# Schematic.net
KiCad netlist of a schematic drawn in EAGLE
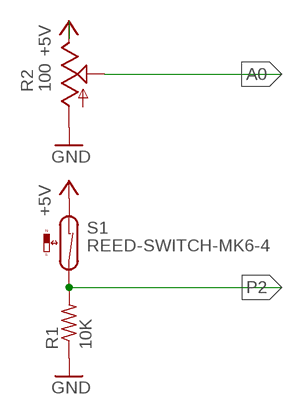
[diagram p0: schematic, sheet 1]

(export (version "E")
  (design (tool "Eeschema 10.0.6"))
  (components
    (comp (ref "R1")
      (value "10K")
      (footprint "eagle-import:0204_5")
      (libsource (lib "eagle-import") (part "R-US_0204/5"))
    )
    (comp (ref "R2")
      (value "100")
      (footprint "eagle-import:CIP20C-4MM")
      (libsource (lib "eagle-import") (part "TRIM_US-CIP20C-4MM"))
    )
    (comp (ref "S1")
      (value "REED-SWITCH-MK6-4")
      (footprint "eagle-import:MK6-4")
      (libsource (lib "eagle-import") (part "REED-SWITCH-MK6-4"))
    )
  )
  (nets
    (net (code "1") (name "+5V") (class "Default")
      (node (ref "R2") (pin "E") (pinfunction "E_E") (pintype "passive"))
      (node (ref "S1") (pin "1") (pinfunction "1_1") (pintype "passive"))
    )
    (net (code "2") (name "A0") (class "Default")
      (node (ref "R2") (pin "S") (pinfunction "S_S") (pintype "passive"))
    )
    (net (code "3") (name "GND") (class "Default")
      (node (ref "R1") (pin "1") (pinfunction "1_1") (pintype "passive"))
      (node (ref "R2") (pin "A") (pinfunction "A_A") (pintype "passive"))
    )
    (net (code "4") (name "P2") (class "Default")
      (node (ref "R1") (pin "2") (pinfunction "2_2") (pintype "passive"))
      (node (ref "S1") (pin "2") (pinfunction "2_2") (pintype "passive"))
    )
  )
)
